# ArduinoPCB.net
KiCad netlist of a schematic drawn in EAGLE
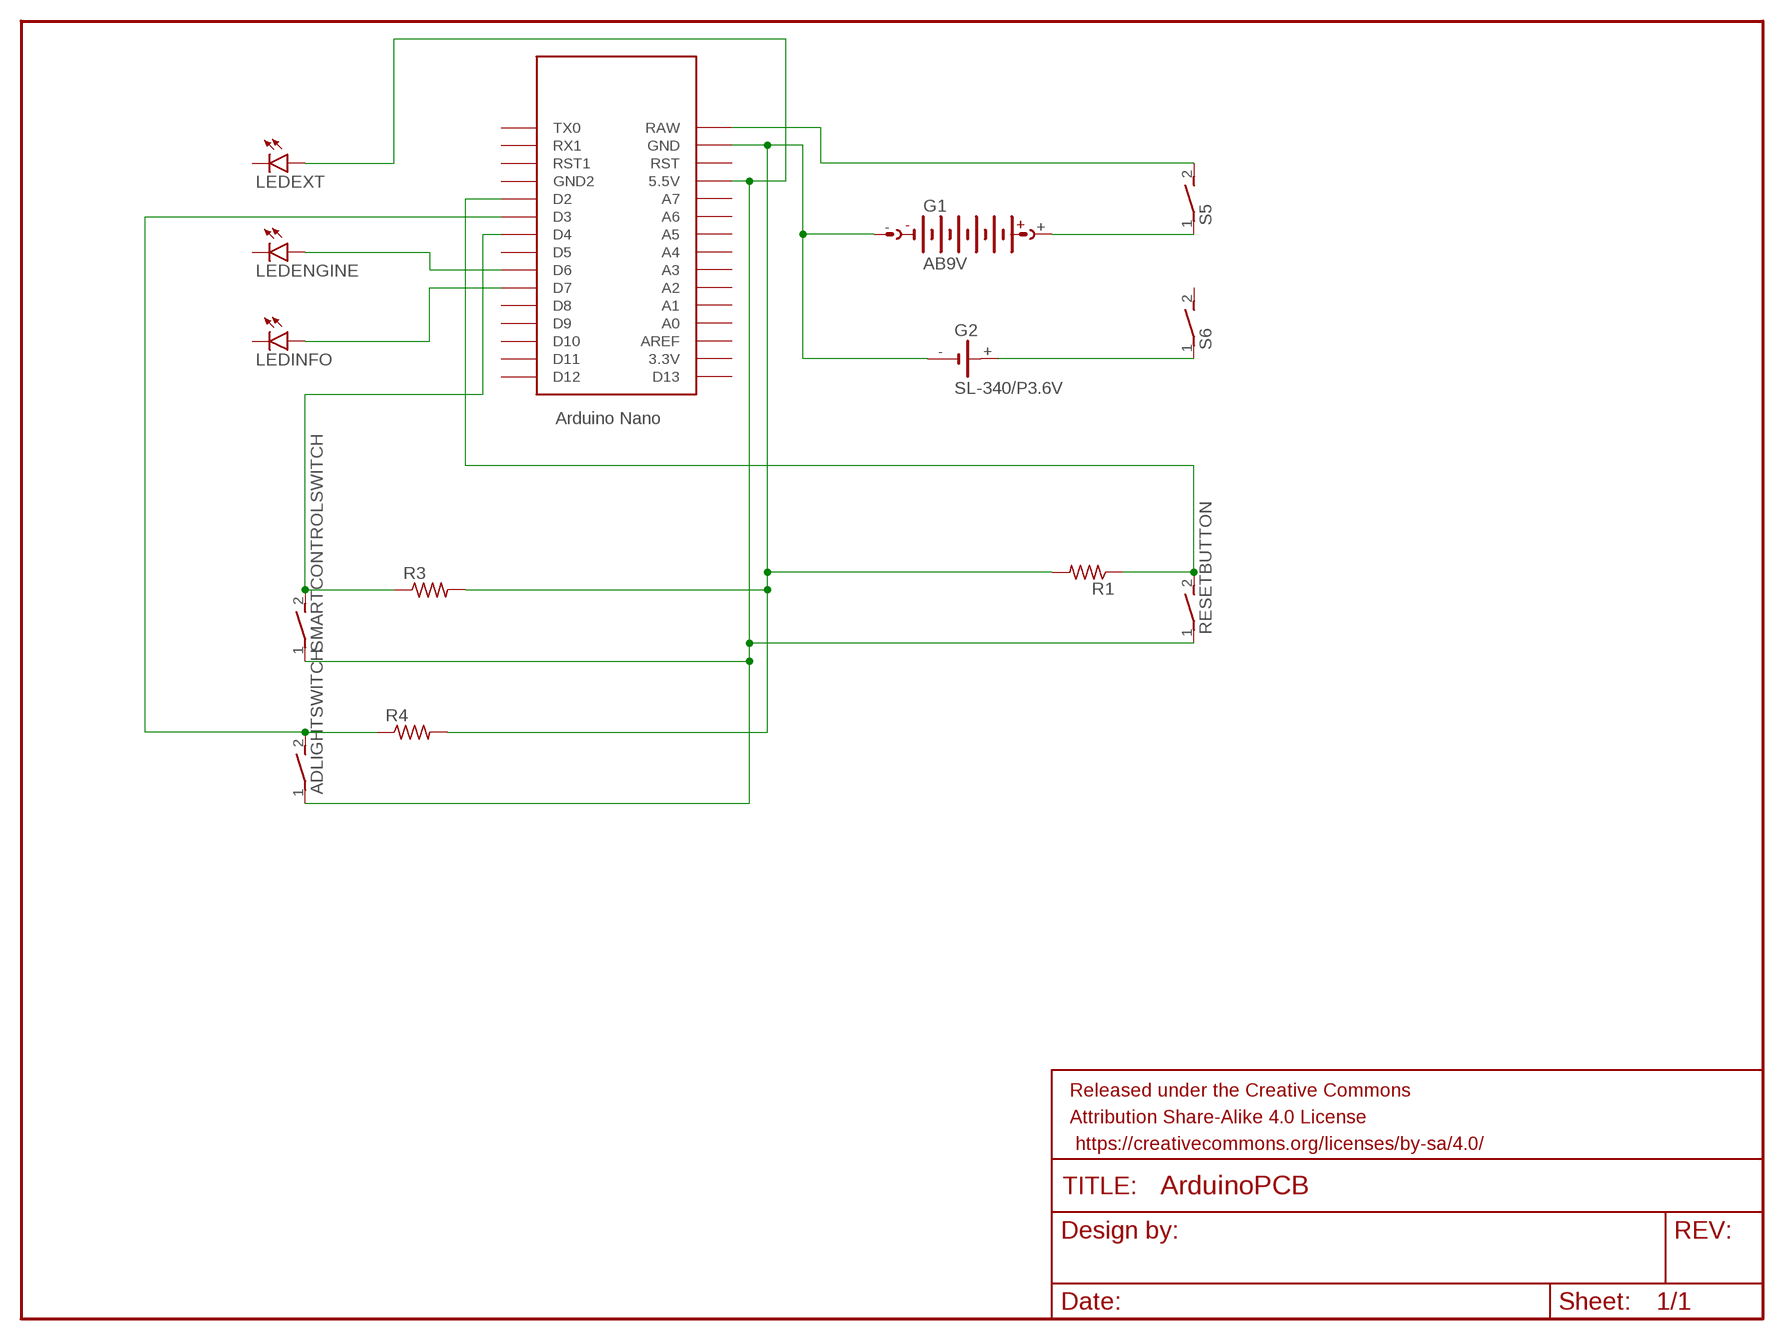
[diagram p0: schematic, sheet 1]

(export (version "E")
  (design (tool "Eeschema 10.0.6"))
  (components
    (comp (ref "ADLIGHTSWITCH")
      (value "DS01E")
      (footprint "eagle-import:DS-01")
      (libsource (lib "eagle-import") (part "DS01E"))
    )
    (comp (ref "FRAME1")
      (value "FRAME-LETTER")
      (footprint "eagle-import:CREATIVE_COMMONS")
      (libsource (lib "eagle-import") (part "FRAME-LETTER"))
    )
    (comp (ref "G1")
      (value "AB9V")
      (footprint "eagle-import:AB9V")
      (libsource (lib "eagle-import") (part "AB9V"))
    )
    (comp (ref "G2")
      (value "SL-340/P3.6V")
      (footprint "eagle-import:SL-340_P3.6V")
      (libsource (lib "eagle-import") (part "SL-340/P3.6V"))
    )
    (comp (ref "LEDENGINE")
      (value "LED3MM")
      (footprint "eagle-import:LED3MM")
      (libsource (lib "eagle-import") (part "LED3MM"))
    )
    (comp (ref "LEDEXT")
      (value "LED3MM")
      (footprint "eagle-import:LED3MM")
      (libsource (lib "eagle-import") (part "LED3MM"))
    )
    (comp (ref "LEDINFO")
      (value "LED3MM")
      (footprint "eagle-import:LED3MM")
      (libsource (lib "eagle-import") (part "LED3MM"))
    )
    (comp (ref "R1")
      (value "R-US_0309/12")
      (footprint "eagle-import:0309_12")
      (libsource (lib "eagle-import") (part "R-US_0309/12"))
    )
    (comp (ref "R3")
      (value "R-US_0309/12")
      (footprint "eagle-import:0309_12")
      (libsource (lib "eagle-import") (part "R-US_0309/12"))
    )
    (comp (ref "R4")
      (value "R-US_0309/12")
      (footprint "eagle-import:0309_12")
      (libsource (lib "eagle-import") (part "R-US_0309/12"))
    )
    (comp (ref "RESETBUTTON")
      (value "DS01E")
      (footprint "eagle-import:DS-01")
      (libsource (lib "eagle-import") (part "DS01E"))
    )
    (comp (ref "S5")
      (value "DS01E")
      (footprint "eagle-import:DS-01")
      (libsource (lib "eagle-import") (part "DS01E"))
    )
    (comp (ref "S6")
      (value "DS01E")
      (footprint "eagle-import:DS-01")
      (libsource (lib "eagle-import") (part "DS01E"))
    )
    (comp (ref "SMARTCONTROLSWITCH")
      (value "DS01E")
      (footprint "eagle-import:DS-01")
      (libsource (lib "eagle-import") (part "DS01E"))
    )
    (comp (ref "U$1")
      (value "NANO")
      (footprint "eagle-import:NANO")
      (libsource (lib "eagle-import") (part "NANO"))
    )
  )
  (nets
    (net (code "1") (name "Net-(ADLIGHTSWITCH-Pad2)") (class "Default")
      (node (ref "ADLIGHTSWITCH") (pin "2") (pinfunction "2_2") (pintype "passive"))
      (node (ref "R4") (pin "1") (pinfunction "1_1") (pintype "passive"))
      (node (ref "U$1") (pin "D3") (pinfunction "D3_D3") (pintype "bidirectional"))
    )
    (net (code "2") (name "Net-(G1-Pad+)") (class "Default")
      (node (ref "G1") (pin "+") (pinfunction "+_+") (pintype "passive"))
      (node (ref "S5") (pin "1") (pinfunction "1_1") (pintype "passive"))
    )
    (net (code "3") (name "Net-(G1-Pad-)") (class "Default")
      (node (ref "G1") (pin "-") (pinfunction "-_-") (pintype "passive"))
      (node (ref "G2") (pin "-") (pinfunction "-_-") (pintype "passive"))
      (node (ref "R1") (pin "2") (pinfunction "2_2") (pintype "passive"))
      (node (ref "R3") (pin "2") (pinfunction "2_2") (pintype "passive"))
      (node (ref "R4") (pin "2") (pinfunction "2_2") (pintype "passive"))
      (node (ref "U$1") (pin "GND") (pinfunction "GND_GND") (pintype "bidirectional"))
    )
    (net (code "4") (name "Net-(G2-Pad+)") (class "Default")
      (node (ref "G2") (pin "+") (pinfunction "+_+") (pintype "passive"))
      (node (ref "S6") (pin "1") (pinfunction "1_1") (pintype "passive"))
    )
    (net (code "5") (name "Net-(LEDENGINE-PadA)") (class "Default")
      (node (ref "LEDENGINE") (pin "A") (pinfunction "A_A") (pintype "passive"))
      (node (ref "U$1") (pin "D6") (pinfunction "D6_D6") (pintype "bidirectional"))
    )
    (net (code "6") (name "Net-(LEDINFO-PadA)") (class "Default")
      (node (ref "LEDINFO") (pin "A") (pinfunction "A_A") (pintype "passive"))
      (node (ref "U$1") (pin "D7") (pinfunction "D7_D7") (pintype "bidirectional"))
    )
    (net (code "7") (name "Net-(R1-Pad1)") (class "Default")
      (node (ref "R1") (pin "1") (pinfunction "1_1") (pintype "passive"))
      (node (ref "RESETBUTTON") (pin "2") (pinfunction "2_2") (pintype "passive"))
      (node (ref "U$1") (pin "D2") (pinfunction "D2_D2") (pintype "bidirectional"))
    )
    (net (code "8") (name "Net-(R3-Pad1)") (class "Default")
      (node (ref "R3") (pin "1") (pinfunction "1_1") (pintype "passive"))
      (node (ref "SMARTCONTROLSWITCH") (pin "2") (pinfunction "2_2") (pintype "passive"))
      (node (ref "U$1") (pin "D4") (pinfunction "D4_D4") (pintype "bidirectional"))
    )
    (net (code "9") (name "Net-(S5-Pad2)") (class "Default")
      (node (ref "S5") (pin "2") (pinfunction "2_2") (pintype "passive"))
      (node (ref "U$1") (pin "RAW") (pinfunction "RAW_RAW") (pintype "bidirectional"))
    )
    (net (code "10") (name "Net-(U$1-5.5V)") (class "Default")
      (node (ref "ADLIGHTSWITCH") (pin "1") (pinfunction "1_1") (pintype "passive"))
      (node (ref "LEDEXT") (pin "A") (pinfunction "A_A") (pintype "passive"))
      (node (ref "RESETBUTTON") (pin "1") (pinfunction "1_1") (pintype "passive"))
      (node (ref "SMARTCONTROLSWITCH") (pin "1") (pinfunction "1_1") (pintype "passive"))
      (node (ref "U$1") (pin "5V") (pinfunction "5.5V_5V") (pintype "bidirectional"))
    )
    (net (code "11") (name "unconnected-(LEDENGINE-C-PadK)") (class "Default")
      (node (ref "LEDENGINE") (pin "K") (pinfunction "C_K") (pintype "passive"))
    )
    (net (code "12") (name "unconnected-(LEDEXT-C-PadK)") (class "Default")
      (node (ref "LEDEXT") (pin "K") (pinfunction "C_K") (pintype "passive"))
    )
    (net (code "13") (name "unconnected-(LEDINFO-C-PadK)") (class "Default")
      (node (ref "LEDINFO") (pin "K") (pinfunction "C_K") (pintype "passive"))
    )
    (net (code "14") (name "unconnected-(S6-Pad2)") (class "Default")
      (node (ref "S6") (pin "2") (pinfunction "2_2") (pintype "passive"))
    )
    (net (code "15") (name "unconnected-(U$1-GND2-PadGND1)") (class "Default")
      (node (ref "U$1") (pin "GND1") (pinfunction "GND2_GND1") (pintype "bidirectional"))
    )
    (net (code "16") (name "unconnected-(U$1-Pad3.3V)") (class "Default")
      (node (ref "U$1") (pin "3.3V") (pinfunction "3.3V_3.3V") (pintype "bidirectional"))
    )
    (net (code "17") (name "unconnected-(U$1-PadA0)") (class "Default")
      (node (ref "U$1") (pin "A0") (pinfunction "A0_A0") (pintype "bidirectional"))
    )
    (net (code "18") (name "unconnected-(U$1-PadA1)") (class "Default")
      (node (ref "U$1") (pin "A1") (pinfunction "A1_A1") (pintype "bidirectional"))
    )
    (net (code "19") (name "unconnected-(U$1-PadA2)") (class "Default")
      (node (ref "U$1") (pin "A2") (pinfunction "A2_A2") (pintype "bidirectional"))
    )
    (net (code "20") (name "unconnected-(U$1-PadA3)") (class "Default")
      (node (ref "U$1") (pin "A3") (pinfunction "A3_A3") (pintype "bidirectional"))
    )
    (net (code "21") (name "unconnected-(U$1-PadA4)") (class "Default")
      (node (ref "U$1") (pin "A4") (pinfunction "A4_A4") (pintype "bidirectional"))
    )
    (net (code "22") (name "unconnected-(U$1-PadA5)") (class "Default")
      (node (ref "U$1") (pin "A5") (pinfunction "A5_A5") (pintype "bidirectional"))
    )
    (net (code "23") (name "unconnected-(U$1-PadA6)") (class "Default")
      (node (ref "U$1") (pin "A6") (pinfunction "A6_A6") (pintype "bidirectional"))
    )
    (net (code "24") (name "unconnected-(U$1-PadA7)") (class "Default")
      (node (ref "U$1") (pin "A7") (pinfunction "A7_A7") (pintype "bidirectional"))
    )
    (net (code "25") (name "unconnected-(U$1-PadAREF)") (class "Default")
      (node (ref "U$1") (pin "AREF") (pinfunction "AREF_AREF") (pintype "bidirectional"))
    )
    (net (code "26") (name "unconnected-(U$1-PadD5)") (class "Default")
      (node (ref "U$1") (pin "D5") (pinfunction "D5_D5") (pintype "bidirectional"))
    )
    (net (code "27") (name "unconnected-(U$1-PadD8)") (class "Default")
      (node (ref "U$1") (pin "D8") (pinfunction "D8_D8") (pintype "bidirectional"))
    )
    (net (code "28") (name "unconnected-(U$1-PadD9)") (class "Default")
      (node (ref "U$1") (pin "D9") (pinfunction "D9_D9") (pintype "bidirectional"))
    )
    (net (code "29") (name "unconnected-(U$1-PadD10)") (class "Default")
      (node (ref "U$1") (pin "D10") (pinfunction "D10_D10") (pintype "bidirectional"))
    )
    (net (code "30") (name "unconnected-(U$1-PadD11)") (class "Default")
      (node (ref "U$1") (pin "D11") (pinfunction "D11_D11") (pintype "bidirectional"))
    )
    (net (code "31") (name "unconnected-(U$1-PadD12)") (class "Default")
      (node (ref "U$1") (pin "D12") (pinfunction "D12_D12") (pintype "bidirectional"))
    )
    (net (code "32") (name "unconnected-(U$1-PadD13)") (class "Default")
      (node (ref "U$1") (pin "D13") (pinfunction "D13_D13") (pintype "bidirectional"))
    )
    (net (code "33") (name "unconnected-(U$1-PadICSP1)") (class "Default")
      (node (ref "U$1") (pin "ICSP1") (pinfunction "ICSP1_ICSP1") (pintype "bidirectional"))
    )
    (net (code "34") (name "unconnected-(U$1-PadICSP2)") (class "Default")
      (node (ref "U$1") (pin "ICSP2") (pinfunction "ICSP2_ICSP2") (pintype "bidirectional"))
    )
    (net (code "35") (name "unconnected-(U$1-PadICSP3)") (class "Default")
      (node (ref "U$1") (pin "ICSP3") (pinfunction "ICSP3_ICSP3") (pintype "bidirectional"))
    )
    (net (code "36") (name "unconnected-(U$1-PadICSP4)") (class "Default")
      (node (ref "U$1") (pin "ICSP4") (pinfunction "ICSP4_ICSP4") (pintype "bidirectional"))
    )
    (net (code "37") (name "unconnected-(U$1-PadICSP5)") (class "Default")
      (node (ref "U$1") (pin "ICSP5") (pinfunction "ICSP5_ICSP5") (pintype "bidirectional"))
    )
    (net (code "38") (name "unconnected-(U$1-PadICSP6)") (class "Default")
      (node (ref "U$1") (pin "ICSP6") (pinfunction "ICSP6_ICSP6") (pintype "bidirectional"))
    )
    (net (code "39") (name "unconnected-(U$1-PadRST)") (class "Default")
      (node (ref "U$1") (pin "RST") (pinfunction "RST_RST") (pintype "bidirectional"))
    )
    (net (code "40") (name "unconnected-(U$1-PadRST1)") (class "Default")
      (node (ref "U$1") (pin "RST1") (pinfunction "RST1_RST1") (pintype "bidirectional"))
    )
    (net (code "41") (name "unconnected-(U$1-PadRX1)") (class "Default")
      (node (ref "U$1") (pin "RX1") (pinfunction "RX1_RX1") (pintype "bidirectional"))
    )
    (net (code "42") (name "unconnected-(U$1-PadTX0)") (class "Default")
      (node (ref "U$1") (pin "TX0") (pinfunction "TX0_TX0") (pintype "bidirectional"))
    )
  )
)
